# motherboard_v4.net
KiCad netlist of a schematic drawn in EAGLE
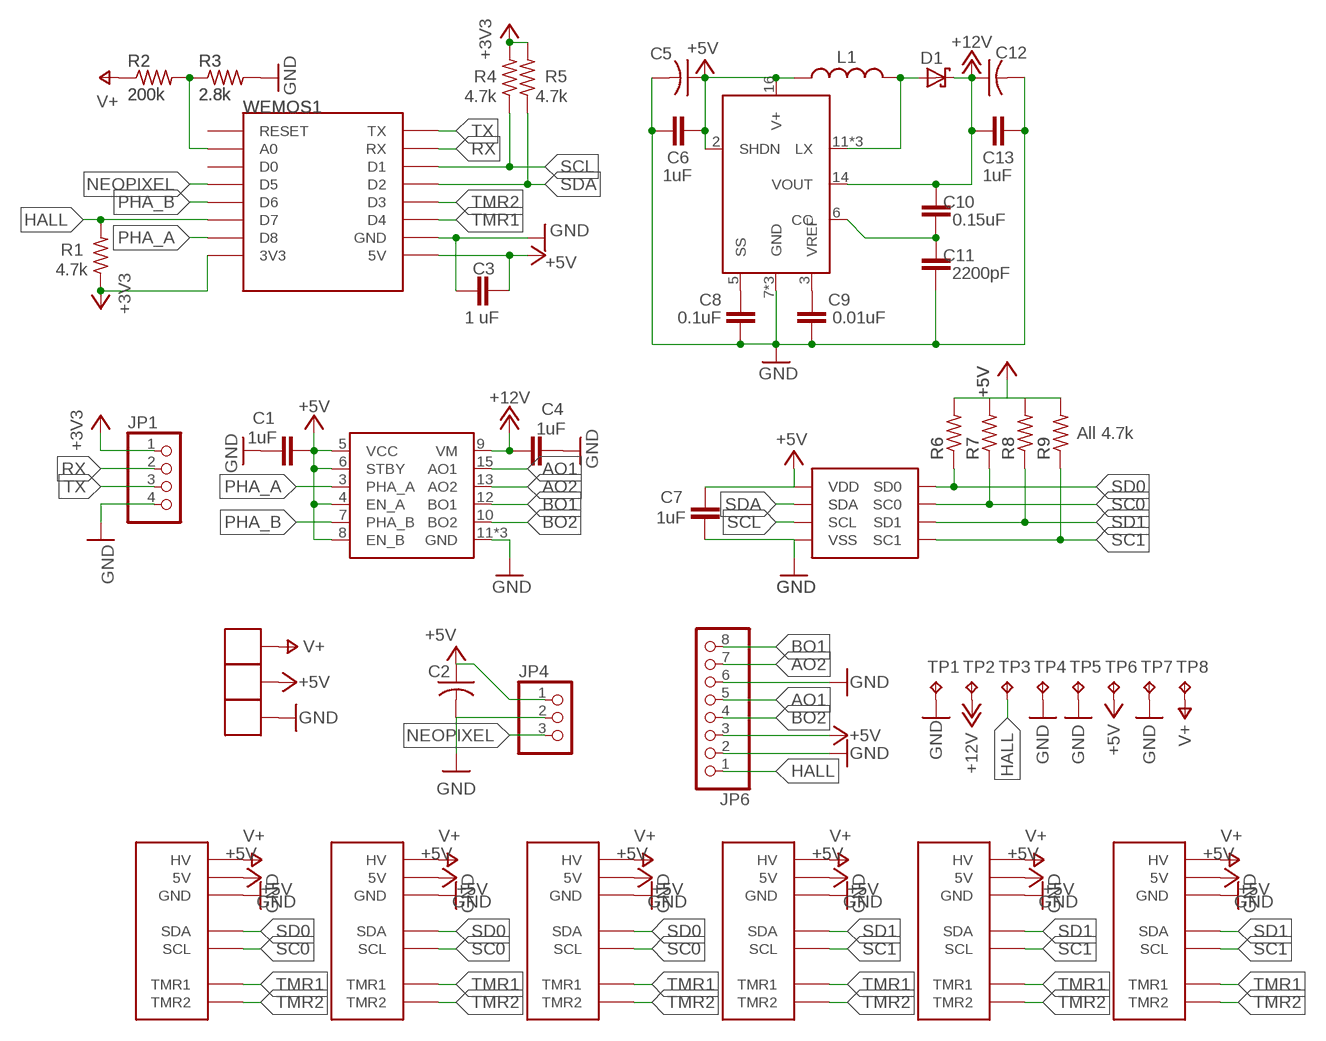
[diagram p0: schematic, sheet 1]

(export (version "E")
  (design (tool "Eeschema 10.0.6"))
  (components
    (comp (ref "C1")
      (value "1uF")
      (footprint "eagle-import:C1206")
      (libsource (lib "eagle-import") (part "C-EUC1206"))
    )
    (comp (ref "C2")
      (value "UCM1H331MNL1GS")
      (footprint "eagle-import:CAPAE1030X1050")
      (libsource (lib "eagle-import") (part "UCM1H331MNL1GS"))
    )
    (comp (ref "C3")
      (value "1 uF")
      (footprint "eagle-import:C1206")
      (libsource (lib "eagle-import") (part "C-EUC1206"))
    )
    (comp (ref "C4")
      (value "1uF")
      (footprint "eagle-import:C1206")
      (libsource (lib "eagle-import") (part "C-EUC1206"))
    )
    (comp (ref "C5")
      (value "UCM1H331MNL1GS")
      (footprint "eagle-import:CAPAE1030X1050")
      (libsource (lib "eagle-import") (part "UCM1H331MNL1GS"))
    )
    (comp (ref "C6")
      (value "1uF")
      (footprint "eagle-import:C1206")
      (libsource (lib "eagle-import") (part "C-EUC1206"))
    )
    (comp (ref "C7")
      (value "1uF")
      (footprint "eagle-import:C1206")
      (libsource (lib "eagle-import") (part "C-EUC1206"))
    )
    (comp (ref "C8")
      (value "0.1uF")
      (footprint "eagle-import:C1206")
      (libsource (lib "eagle-import") (part "C-EUC1206"))
    )
    (comp (ref "C9")
      (value "0.01uF")
      (footprint "eagle-import:C1206")
      (libsource (lib "eagle-import") (part "C-EUC1206"))
    )
    (comp (ref "C10")
      (value "0.15uF")
      (footprint "eagle-import:C1206")
      (libsource (lib "eagle-import") (part "C-EUC1206"))
    )
    (comp (ref "C11")
      (value "2200pF")
      (footprint "eagle-import:C1206")
      (libsource (lib "eagle-import") (part "C-EUC1206"))
    )
    (comp (ref "C12")
      (value "UCM1H331MNL1GS")
      (footprint "eagle-import:CAPAE1030X1050")
      (libsource (lib "eagle-import") (part "UCM1H331MNL1GS"))
    )
    (comp (ref "C13")
      (value "1uF")
      (footprint "eagle-import:C1206")
      (libsource (lib "eagle-import") (part "C-EUC1206"))
    )
    (comp (ref "D1")
      (value "NSR0530H")
      (footprint "eagle-import:SOD2512X100")
      (libsource (lib "eagle-import") (part "NSR0530H"))
    )
    (comp (ref "J1")
      (value "PHOENIX_1731468")
      (footprint "eagle-import:PHOENIX_1731468")
      (libsource (lib "eagle-import") (part "PHOENIX_1731468"))
    )
    (comp (ref "J2")
      (value "PHOENIX_1731468")
      (footprint "eagle-import:PHOENIX_1731468")
      (libsource (lib "eagle-import") (part "PHOENIX_1731468"))
    )
    (comp (ref "J3")
      (value "PHOENIX_1731468")
      (footprint "eagle-import:PHOENIX_1731468")
      (libsource (lib "eagle-import") (part "PHOENIX_1731468"))
    )
    (comp (ref "JP1")
      (value "PINHD-1X4")
      (footprint "eagle-import:1X04")
      (libsource (lib "eagle-import") (part "PINHD-1X4"))
    )
    (comp (ref "JP2")
      (value "PCIE_SOCKET")
      (footprint "eagle-import:PCIE_SOCKET")
      (libsource (lib "eagle-import") (part "PCIE_SOCKET"))
    )
    (comp (ref "JP3")
      (value "PCIE_SOCKET")
      (footprint "eagle-import:PCIE_SOCKET")
      (libsource (lib "eagle-import") (part "PCIE_SOCKET"))
    )
    (comp (ref "JP4")
      (value "PINHD-1X3")
      (footprint "eagle-import:1X03")
      (libsource (lib "eagle-import") (part "PINHD-1X3"))
    )
    (comp (ref "JP5")
      (value "PCIE_SOCKET")
      (footprint "eagle-import:PCIE_SOCKET")
      (libsource (lib "eagle-import") (part "PCIE_SOCKET"))
    )
    (comp (ref "JP6")
      (value "PINHD-1X8")
      (footprint "eagle-import:1X08")
      (libsource (lib "eagle-import") (part "PINHD-1X8"))
    )
    (comp (ref "JP7")
      (value "PCIE_SOCKET")
      (footprint "eagle-import:PCIE_SOCKET")
      (libsource (lib "eagle-import") (part "PCIE_SOCKET"))
    )
    (comp (ref "JP8")
      (value "PCIE_SOCKET")
      (footprint "eagle-import:PCIE_SOCKET")
      (libsource (lib "eagle-import") (part "PCIE_SOCKET"))
    )
    (comp (ref "JP9")
      (value "PCIE_SOCKET")
      (footprint "eagle-import:PCIE_SOCKET")
      (libsource (lib "eagle-import") (part "PCIE_SOCKET"))
    )
    (comp (ref "L1")
      (value "NR6028")
      (footprint "eagle-import:NR6028")
      (libsource (lib "eagle-import") (part "NR6028"))
    )
    (comp (ref "R1")
      (value "4.7k")
      (footprint "eagle-import:R1206")
      (libsource (lib "eagle-import") (part "R-US_R1206"))
    )
    (comp (ref "R2")
      (value "200k")
      (footprint "eagle-import:R1206")
      (libsource (lib "eagle-import") (part "R-US_R1206"))
    )
    (comp (ref "R3")
      (value "2.8k")
      (footprint "eagle-import:R1206")
      (libsource (lib "eagle-import") (part "R-US_R1206"))
    )
    (comp (ref "R4")
      (value "4.7k")
      (footprint "eagle-import:R1206")
      (libsource (lib "eagle-import") (part "R-US_R1206"))
    )
    (comp (ref "R5")
      (value "4.7k")
      (footprint "eagle-import:R1206")
      (libsource (lib "eagle-import") (part "R-US_R1206"))
    )
    (comp (ref "R6")
      (value "R-US_R1206")
      (footprint "eagle-import:R1206")
      (libsource (lib "eagle-import") (part "R-US_R1206"))
    )
    (comp (ref "R7")
      (value "R-US_R1206")
      (footprint "eagle-import:R1206")
      (libsource (lib "eagle-import") (part "R-US_R1206"))
    )
    (comp (ref "R8")
      (value "R-US_R1206")
      (footprint "eagle-import:R1206")
      (libsource (lib "eagle-import") (part "R-US_R1206"))
    )
    (comp (ref "R9")
      (value "R-US_R1206")
      (footprint "eagle-import:R1206")
      (libsource (lib "eagle-import") (part "R-US_R1206"))
    )
    (comp (ref "TP1")
      (value "TPB2,54")
      (footprint "eagle-import:B2,54")
      (libsource (lib "eagle-import") (part "TPB2,54"))
    )
    (comp (ref "TP2")
      (value "TPB2,54")
      (footprint "eagle-import:B2,54")
      (libsource (lib "eagle-import") (part "TPB2,54"))
    )
    (comp (ref "TP3")
      (value "TPB2,54")
      (footprint "eagle-import:B2,54")
      (libsource (lib "eagle-import") (part "TPB2,54"))
    )
    (comp (ref "TP4")
      (value "TPB2,54")
      (footprint "eagle-import:B2,54")
      (libsource (lib "eagle-import") (part "TPB2,54"))
    )
    (comp (ref "TP5")
      (value "TPB2,54")
      (footprint "eagle-import:B2,54")
      (libsource (lib "eagle-import") (part "TPB2,54"))
    )
    (comp (ref "TP6")
      (value "TPB2,54")
      (footprint "eagle-import:B2,54")
      (libsource (lib "eagle-import") (part "TPB2,54"))
    )
    (comp (ref "TP7")
      (value "TPB2,54")
      (footprint "eagle-import:B2,54")
      (libsource (lib "eagle-import") (part "TPB2,54"))
    )
    (comp (ref "TP8")
      (value "TPB2,54")
      (footprint "eagle-import:B2,54")
      (libsource (lib "eagle-import") (part "TPB2,54"))
    )
    (comp (ref "U1")
      (value "TC78H620FNG")
      (footprint "eagle-import:SSOP16")
      (libsource (lib "eagle-import") (part "TC78H620FNG"))
    )
    (comp (ref "U2")
      (value "MAX732")
      (footprint "eagle-import:SOIC127P1032X265-16")
      (libsource (lib "eagle-import") (part "MAX732"))
    )
    (comp (ref "U3")
      (value "PCA9540BDPSOIC8")
      (footprint "eagle-import:SOIC127P599X175-8")
      (libsource (lib "eagle-import") (part "PCA9540BDPSOIC8"))
    )
    (comp (ref "WEMOS1")
      (value "WEMOS-D1-MINISMD")
      (footprint "eagle-import:WEMOS-D1-MINI-SMD")
      (libsource (lib "eagle-import") (part "WEMOS-D1-MINISMD"))
    )
  )
  (nets
    (net (code "1") (name "+3V3") (class "Default")
      (node (ref "JP1") (pin "1") (pinfunction "1_1") (pintype "passive"))
      (node (ref "R1") (pin "1") (pinfunction "1_1") (pintype "passive"))
      (node (ref "R4") (pin "2") (pinfunction "2_2") (pintype "passive"))
      (node (ref "R5") (pin "2") (pinfunction "2_2") (pintype "passive"))
      (node (ref "WEMOS1") (pin "3V3") (pinfunction "3V3_3V3") (pintype "bidirectional"))
    )
    (net (code "2") (name "+5V") (class "Default")
      (node (ref "C1") (pin "2") (pinfunction "2_2") (pintype "passive"))
      (node (ref "C2") (pin "1") (pinfunction "1_1") (pintype "passive"))
      (node (ref "C3") (pin "2") (pinfunction "2_2") (pintype "passive"))
      (node (ref "C5") (pin "1") (pinfunction "1_1") (pintype "passive"))
      (node (ref "C6") (pin "1") (pinfunction "1_1") (pintype "passive"))
      (node (ref "C7") (pin "2") (pinfunction "2_2") (pintype "passive"))
      (node (ref "J2") (pin "P$1") (pinfunction "P$1_P$1") (pintype "bidirectional"))
      (node (ref "J2") (pin "P$2") (pinfunction "P$1_P$2") (pintype "bidirectional"))
      (node (ref "JP2") (pin "5V1") (pinfunction "5V_5V1") (pintype "passive"))
      (node (ref "JP2") (pin "5V2") (pinfunction "5V_5V2") (pintype "passive"))
      (node (ref "JP3") (pin "5V1") (pinfunction "5V_5V1") (pintype "passive"))
      (node (ref "JP3") (pin "5V2") (pinfunction "5V_5V2") (pintype "passive"))
      (node (ref "JP4") (pin "1") (pinfunction "1_1") (pintype "passive"))
      (node (ref "JP5") (pin "5V1") (pinfunction "5V_5V1") (pintype "passive"))
      (node (ref "JP5") (pin "5V2") (pinfunction "5V_5V2") (pintype "passive"))
      (node (ref "JP6") (pin "3") (pinfunction "3_3") (pintype "passive"))
      (node (ref "JP7") (pin "5V1") (pinfunction "5V_5V1") (pintype "passive"))
      (node (ref "JP7") (pin "5V2") (pinfunction "5V_5V2") (pintype "passive"))
      (node (ref "JP8") (pin "5V1") (pinfunction "5V_5V1") (pintype "passive"))
      (node (ref "JP8") (pin "5V2") (pinfunction "5V_5V2") (pintype "passive"))
      (node (ref "JP9") (pin "5V1") (pinfunction "5V_5V1") (pintype "passive"))
      (node (ref "JP9") (pin "5V2") (pinfunction "5V_5V2") (pintype "passive"))
      (node (ref "L1") (pin "1") (pinfunction "1_1") (pintype "passive"))
      (node (ref "R6") (pin "2") (pinfunction "2_2") (pintype "passive"))
      (node (ref "R7") (pin "2") (pinfunction "2_2") (pintype "passive"))
      (node (ref "R8") (pin "2") (pinfunction "2_2") (pintype "passive"))
      (node (ref "R9") (pin "2") (pinfunction "2_2") (pintype "passive"))
      (node (ref "TP6") (pin "TP") (pinfunction "TP_TP") (pintype "input"))
      (node (ref "U1") (pin "4") (pinfunction "EN_A_4") (pintype "bidirectional"))
      (node (ref "U1") (pin "5") (pinfunction "VCC_5") (pintype "bidirectional"))
      (node (ref "U1") (pin "6") (pinfunction "STBY_6") (pintype "bidirectional"))
      (node (ref "U1") (pin "8") (pinfunction "EN_B_8") (pintype "bidirectional"))
      (node (ref "U2") (pin "16") (pinfunction "V+_16") (pintype "passive"))
      (node (ref "U2") (pin "2") (pinfunction "SHDN_2") (pintype "passive"))
      (node (ref "U3") (pin "3") (pinfunction "VDD_3") (pintype "bidirectional"))
      (node (ref "WEMOS1") (pin "5V") (pinfunction "5V_5V") (pintype "bidirectional"))
    )
    (net (code "3") (name "+12V") (class "Default")
      (node (ref "C10") (pin "2") (pinfunction "2_2") (pintype "passive"))
      (node (ref "C12") (pin "1") (pinfunction "1_1") (pintype "passive"))
      (node (ref "C13") (pin "2") (pinfunction "2_2") (pintype "passive"))
      (node (ref "C4") (pin "1") (pinfunction "1_1") (pintype "passive"))
      (node (ref "D1") (pin "1") (pinfunction "C_1") (pintype "passive"))
      (node (ref "TP2") (pin "TP") (pinfunction "TP_TP") (pintype "input"))
      (node (ref "U1") (pin "9") (pinfunction "VM_9") (pintype "bidirectional"))
      (node (ref "U2") (pin "14") (pinfunction "VOUT_14") (pintype "passive"))
    )
    (net (code "4") (name "AO1") (class "Default")
      (node (ref "JP6") (pin "5") (pinfunction "5_5") (pintype "passive"))
      (node (ref "U1") (pin "15") (pinfunction "AO1_15") (pintype "bidirectional"))
    )
    (net (code "5") (name "AO2") (class "Default")
      (node (ref "JP6") (pin "7") (pinfunction "7_7") (pintype "passive"))
      (node (ref "U1") (pin "13") (pinfunction "AO2_13") (pintype "bidirectional"))
    )
    (net (code "6") (name "BO1") (class "Default")
      (node (ref "JP6") (pin "8") (pinfunction "8_8") (pintype "passive"))
      (node (ref "U1") (pin "12") (pinfunction "BO1_12") (pintype "bidirectional"))
    )
    (net (code "7") (name "BO2") (class "Default")
      (node (ref "JP6") (pin "4") (pinfunction "4_4") (pintype "passive"))
      (node (ref "U1") (pin "10") (pinfunction "BO2_10") (pintype "bidirectional"))
    )
    (net (code "8") (name "GND") (class "Default")
      (node (ref "C1") (pin "1") (pinfunction "1_1") (pintype "passive"))
      (node (ref "C11") (pin "1") (pinfunction "1_1") (pintype "passive"))
      (node (ref "C12") (pin "2") (pinfunction "2_2") (pintype "passive"))
      (node (ref "C13") (pin "1") (pinfunction "1_1") (pintype "passive"))
      (node (ref "C2") (pin "2") (pinfunction "2_2") (pintype "passive"))
      (node (ref "C3") (pin "1") (pinfunction "1_1") (pintype "passive"))
      (node (ref "C4") (pin "2") (pinfunction "2_2") (pintype "passive"))
      (node (ref "C5") (pin "2") (pinfunction "2_2") (pintype "passive"))
      (node (ref "C6") (pin "2") (pinfunction "2_2") (pintype "passive"))
      (node (ref "C7") (pin "1") (pinfunction "1_1") (pintype "passive"))
      (node (ref "C8") (pin "1") (pinfunction "1_1") (pintype "passive"))
      (node (ref "C9") (pin "1") (pinfunction "1_1") (pintype "passive"))
      (node (ref "J3") (pin "P$1") (pinfunction "P$1_P$1") (pintype "bidirectional"))
      (node (ref "J3") (pin "P$2") (pinfunction "P$1_P$2") (pintype "bidirectional"))
      (node (ref "JP1") (pin "4") (pinfunction "4_4") (pintype "passive"))
      (node (ref "JP2") (pin "GND1") (pinfunction "GND_GND1") (pintype "passive"))
      (node (ref "JP2") (pin "GND2") (pinfunction "GND_GND2") (pintype "passive"))
      (node (ref "JP3") (pin "GND1") (pinfunction "GND_GND1") (pintype "passive"))
      (node (ref "JP3") (pin "GND2") (pinfunction "GND_GND2") (pintype "passive"))
      (node (ref "JP4") (pin "2") (pinfunction "2_2") (pintype "passive"))
      (node (ref "JP5") (pin "GND1") (pinfunction "GND_GND1") (pintype "passive"))
      (node (ref "JP5") (pin "GND2") (pinfunction "GND_GND2") (pintype "passive"))
      (node (ref "JP6") (pin "2") (pinfunction "2_2") (pintype "passive"))
      (node (ref "JP6") (pin "6") (pinfunction "6_6") (pintype "passive"))
      (node (ref "JP7") (pin "GND1") (pinfunction "GND_GND1") (pintype "passive"))
      (node (ref "JP7") (pin "GND2") (pinfunction "GND_GND2") (pintype "passive"))
      (node (ref "JP8") (pin "GND1") (pinfunction "GND_GND1") (pintype "passive"))
      (node (ref "JP8") (pin "GND2") (pinfunction "GND_GND2") (pintype "passive"))
      (node (ref "JP9") (pin "GND1") (pinfunction "GND_GND1") (pintype "passive"))
      (node (ref "JP9") (pin "GND2") (pinfunction "GND_GND2") (pintype "passive"))
      (node (ref "R3") (pin "2") (pinfunction "2_2") (pintype "passive"))
      (node (ref "TP1") (pin "TP") (pinfunction "TP_TP") (pintype "input"))
      (node (ref "TP4") (pin "TP") (pinfunction "TP_TP") (pintype "input"))
      (node (ref "TP5") (pin "TP") (pinfunction "TP_TP") (pintype "input"))
      (node (ref "TP7") (pin "TP") (pinfunction "TP_TP") (pintype "input"))
      (node (ref "U1") (pin "11") (pinfunction "GND_11") (pintype "bidirectional"))
      (node (ref "U1") (pin "14") (pinfunction "GND_14") (pintype "bidirectional"))
      (node (ref "U1") (pin "16") (pinfunction "GND_16") (pintype "bidirectional"))
      (node (ref "U2") (pin "7") (pinfunction "GND_7") (pintype "passive"))
      (node (ref "U2") (pin "8") (pinfunction "GND_8") (pintype "passive"))
      (node (ref "U2") (pin "9") (pinfunction "GND_9") (pintype "passive"))
      (node (ref "U3") (pin "6") (pinfunction "VSS_6") (pintype "bidirectional"))
      (node (ref "WEMOS1") (pin "GND") (pinfunction "GND_GND") (pintype "bidirectional"))
    )
    (net (code "9") (name "HALL") (class "Default")
      (node (ref "JP6") (pin "1") (pinfunction "1_1") (pintype "passive"))
      (node (ref "R1") (pin "2") (pinfunction "2_2") (pintype "passive"))
      (node (ref "TP3") (pin "TP") (pinfunction "TP_TP") (pintype "input"))
      (node (ref "WEMOS1") (pin "D7") (pinfunction "D7_D7") (pintype "bidirectional"))
    )
    (net (code "10") (name "NEOPIXEL") (class "Default")
      (node (ref "JP4") (pin "3") (pinfunction "3_3") (pintype "passive"))
      (node (ref "WEMOS1") (pin "D5") (pinfunction "D5_D5") (pintype "bidirectional"))
    )
    (net (code "11") (name "Net-(D1-A)") (class "Default")
      (node (ref "D1") (pin "2") (pinfunction "A_2") (pintype "passive"))
      (node (ref "L1") (pin "2") (pinfunction "2_2") (pintype "passive"))
      (node (ref "U2") (pin "11") (pinfunction "LX_11") (pintype "passive"))
      (node (ref "U2") (pin "12") (pinfunction "LX_12") (pintype "passive"))
      (node (ref "U2") (pin "13") (pinfunction "LX_13") (pintype "passive"))
    )
    (net (code "12") (name "Net-(R2-Pad2)") (class "Default")
      (node (ref "R2") (pin "2") (pinfunction "2_2") (pintype "passive"))
      (node (ref "R3") (pin "1") (pinfunction "1_1") (pintype "passive"))
      (node (ref "WEMOS1") (pin "A0") (pinfunction "A0_A0") (pintype "bidirectional"))
    )
    (net (code "13") (name "Net-(U2-CC)") (class "Default")
      (node (ref "C10") (pin "1") (pinfunction "1_1") (pintype "passive"))
      (node (ref "C11") (pin "2") (pinfunction "2_2") (pintype "passive"))
      (node (ref "U2") (pin "6") (pinfunction "CC_6") (pintype "passive"))
    )
    (net (code "14") (name "Net-(U2-SS)") (class "Default")
      (node (ref "C8") (pin "2") (pinfunction "2_2") (pintype "passive"))
      (node (ref "U2") (pin "5") (pinfunction "SS_5") (pintype "passive"))
    )
    (net (code "15") (name "Net-(U2-VREF)") (class "Default")
      (node (ref "C9") (pin "2") (pinfunction "2_2") (pintype "passive"))
      (node (ref "U2") (pin "3") (pinfunction "VREF_3") (pintype "passive"))
    )
    (net (code "16") (name "PHA_A") (class "Default")
      (node (ref "U1") (pin "3") (pinfunction "PHA_A_3") (pintype "bidirectional"))
      (node (ref "WEMOS1") (pin "D8") (pinfunction "D8_D8") (pintype "bidirectional"))
    )
    (net (code "17") (name "PHA_B") (class "Default")
      (node (ref "U1") (pin "7") (pinfunction "PHA_B_7") (pintype "bidirectional"))
      (node (ref "WEMOS1") (pin "D6") (pinfunction "D6_D6") (pintype "bidirectional"))
    )
    (net (code "18") (name "RX") (class "Default")
      (node (ref "JP1") (pin "2") (pinfunction "2_2") (pintype "passive"))
      (node (ref "WEMOS1") (pin "RX") (pinfunction "RX_RX") (pintype "bidirectional"))
    )
    (net (code "19") (name "SC0") (class "Default")
      (node (ref "JP2") (pin "SCL1") (pinfunction "SCL_SCL1") (pintype "bidirectional"))
      (node (ref "JP2") (pin "SCL2") (pinfunction "SCL_SCL2") (pintype "bidirectional"))
      (node (ref "JP3") (pin "SCL1") (pinfunction "SCL_SCL1") (pintype "bidirectional"))
      (node (ref "JP3") (pin "SCL2") (pinfunction "SCL_SCL2") (pintype "bidirectional"))
      (node (ref "JP5") (pin "SCL1") (pinfunction "SCL_SCL1") (pintype "bidirectional"))
      (node (ref "JP5") (pin "SCL2") (pinfunction "SCL_SCL2") (pintype "bidirectional"))
      (node (ref "R7") (pin "1") (pinfunction "1_1") (pintype "passive"))
      (node (ref "U3") (pin "5") (pinfunction "SC0_5") (pintype "bidirectional"))
    )
    (net (code "20") (name "SC1") (class "Default")
      (node (ref "JP7") (pin "SCL1") (pinfunction "SCL_SCL1") (pintype "bidirectional"))
      (node (ref "JP7") (pin "SCL2") (pinfunction "SCL_SCL2") (pintype "bidirectional"))
      (node (ref "JP8") (pin "SCL1") (pinfunction "SCL_SCL1") (pintype "bidirectional"))
      (node (ref "JP8") (pin "SCL2") (pinfunction "SCL_SCL2") (pintype "bidirectional"))
      (node (ref "JP9") (pin "SCL1") (pinfunction "SCL_SCL1") (pintype "bidirectional"))
      (node (ref "JP9") (pin "SCL2") (pinfunction "SCL_SCL2") (pintype "bidirectional"))
      (node (ref "R9") (pin "1") (pinfunction "1_1") (pintype "passive"))
      (node (ref "U3") (pin "8") (pinfunction "SC1_8") (pintype "bidirectional"))
    )
    (net (code "21") (name "SCL") (class "Default")
      (node (ref "R4") (pin "1") (pinfunction "1_1") (pintype "passive"))
      (node (ref "U3") (pin "1") (pinfunction "SCL_1") (pintype "bidirectional"))
      (node (ref "WEMOS1") (pin "D1") (pinfunction "D1_D1") (pintype "bidirectional"))
    )
    (net (code "22") (name "SD0") (class "Default")
      (node (ref "JP2") (pin "SDA1") (pinfunction "SDA_SDA1") (pintype "bidirectional"))
      (node (ref "JP2") (pin "SDA2") (pinfunction "SDA_SDA2") (pintype "bidirectional"))
      (node (ref "JP3") (pin "SDA1") (pinfunction "SDA_SDA1") (pintype "bidirectional"))
      (node (ref "JP3") (pin "SDA2") (pinfunction "SDA_SDA2") (pintype "bidirectional"))
      (node (ref "JP5") (pin "SDA1") (pinfunction "SDA_SDA1") (pintype "bidirectional"))
      (node (ref "JP5") (pin "SDA2") (pinfunction "SDA_SDA2") (pintype "bidirectional"))
      (node (ref "R6") (pin "1") (pinfunction "1_1") (pintype "passive"))
      (node (ref "U3") (pin "4") (pinfunction "SD0_4") (pintype "bidirectional"))
    )
    (net (code "23") (name "SD1") (class "Default")
      (node (ref "JP7") (pin "SDA1") (pinfunction "SDA_SDA1") (pintype "bidirectional"))
      (node (ref "JP7") (pin "SDA2") (pinfunction "SDA_SDA2") (pintype "bidirectional"))
      (node (ref "JP8") (pin "SDA1") (pinfunction "SDA_SDA1") (pintype "bidirectional"))
      (node (ref "JP8") (pin "SDA2") (pinfunction "SDA_SDA2") (pintype "bidirectional"))
      (node (ref "JP9") (pin "SDA1") (pinfunction "SDA_SDA1") (pintype "bidirectional"))
      (node (ref "JP9") (pin "SDA2") (pinfunction "SDA_SDA2") (pintype "bidirectional"))
      (node (ref "R8") (pin "1") (pinfunction "1_1") (pintype "passive"))
      (node (ref "U3") (pin "7") (pinfunction "SD1_7") (pintype "bidirectional"))
    )
    (net (code "24") (name "SDA") (class "Default")
      (node (ref "R5") (pin "1") (pinfunction "1_1") (pintype "passive"))
      (node (ref "U3") (pin "2") (pinfunction "SDA_2") (pintype "bidirectional"))
      (node (ref "WEMOS1") (pin "D2") (pinfunction "D2_D2") (pintype "bidirectional"))
    )
    (net (code "25") (name "TMR1") (class "Default")
      (node (ref "JP2") (pin "TMR1_1") (pinfunction "TMR1_TMR1_1") (pintype "bidirectional"))
      (node (ref "JP2") (pin "TMR1_2") (pinfunction "TMR1_TMR1_2") (pintype "bidirectional"))
      (node (ref "JP3") (pin "TMR1_1") (pinfunction "TMR1_TMR1_1") (pintype "bidirectional"))
      (node (ref "JP3") (pin "TMR1_2") (pinfunction "TMR1_TMR1_2") (pintype "bidirectional"))
      (node (ref "JP5") (pin "TMR1_1") (pinfunction "TMR1_TMR1_1") (pintype "bidirectional"))
      (node (ref "JP5") (pin "TMR1_2") (pinfunction "TMR1_TMR1_2") (pintype "bidirectional"))
      (node (ref "JP7") (pin "TMR1_1") (pinfunction "TMR1_TMR1_1") (pintype "bidirectional"))
      (node (ref "JP7") (pin "TMR1_2") (pinfunction "TMR1_TMR1_2") (pintype "bidirectional"))
      (node (ref "JP8") (pin "TMR1_1") (pinfunction "TMR1_TMR1_1") (pintype "bidirectional"))
      (node (ref "JP8") (pin "TMR1_2") (pinfunction "TMR1_TMR1_2") (pintype "bidirectional"))
      (node (ref "JP9") (pin "TMR1_1") (pinfunction "TMR1_TMR1_1") (pintype "bidirectional"))
      (node (ref "JP9") (pin "TMR1_2") (pinfunction "TMR1_TMR1_2") (pintype "bidirectional"))
      (node (ref "WEMOS1") (pin "D4") (pinfunction "D4_D4") (pintype "bidirectional"))
    )
    (net (code "26") (name "TMR2") (class "Default")
      (node (ref "JP2") (pin "TMR2_1") (pinfunction "TMR2_TMR2_1") (pintype "bidirectional"))
      (node (ref "JP2") (pin "TMR2_2") (pinfunction "TMR2_TMR2_2") (pintype "bidirectional"))
      (node (ref "JP3") (pin "TMR2_1") (pinfunction "TMR2_TMR2_1") (pintype "bidirectional"))
      (node (ref "JP3") (pin "TMR2_2") (pinfunction "TMR2_TMR2_2") (pintype "bidirectional"))
      (node (ref "JP5") (pin "TMR2_1") (pinfunction "TMR2_TMR2_1") (pintype "bidirectional"))
      (node (ref "JP5") (pin "TMR2_2") (pinfunction "TMR2_TMR2_2") (pintype "bidirectional"))
      (node (ref "JP7") (pin "TMR2_1") (pinfunction "TMR2_TMR2_1") (pintype "bidirectional"))
      (node (ref "JP7") (pin "TMR2_2") (pinfunction "TMR2_TMR2_2") (pintype "bidirectional"))
      (node (ref "JP8") (pin "TMR2_1") (pinfunction "TMR2_TMR2_1") (pintype "bidirectional"))
      (node (ref "JP8") (pin "TMR2_2") (pinfunction "TMR2_TMR2_2") (pintype "bidirectional"))
      (node (ref "JP9") (pin "TMR2_1") (pinfunction "TMR2_TMR2_1") (pintype "bidirectional"))
      (node (ref "JP9") (pin "TMR2_2") (pinfunction "TMR2_TMR2_2") (pintype "bidirectional"))
      (node (ref "WEMOS1") (pin "D3") (pinfunction "D3_D3") (pintype "bidirectional"))
    )
    (net (code "27") (name "TX") (class "Default")
      (node (ref "JP1") (pin "3") (pinfunction "3_3") (pintype "passive"))
      (node (ref "WEMOS1") (pin "TX") (pinfunction "TX_TX") (pintype "bidirectional"))
    )
    (net (code "28") (name "V+") (class "Default")
      (node (ref "J1") (pin "P$1") (pinfunction "P$1_P$1") (pintype "bidirectional"))
      (node (ref "J1") (pin "P$2") (pinfunction "P$1_P$2") (pintype "bidirectional"))
      (node (ref "JP2") (pin "HV1") (pinfunction "HV_HV1") (pintype "passive"))
      (node (ref "JP2") (pin "HV2") (pinfunction "HV_HV2") (pintype "passive"))
      (node (ref "JP3") (pin "HV1") (pinfunction "HV_HV1") (pintype "passive"))
      (node (ref "JP3") (pin "HV2") (pinfunction "HV_HV2") (pintype "passive"))
      (node (ref "JP5") (pin "HV1") (pinfunction "HV_HV1") (pintype "passive"))
      (node (ref "JP5") (pin "HV2") (pinfunction "HV_HV2") (pintype "passive"))
      (node (ref "JP7") (pin "HV1") (pinfunction "HV_HV1") (pintype "passive"))
      (node (ref "JP7") (pin "HV2") (pinfunction "HV_HV2") (pintype "passive"))
      (node (ref "JP8") (pin "HV1") (pinfunction "HV_HV1") (pintype "passive"))
      (node (ref "JP8") (pin "HV2") (pinfunction "HV_HV2") (pintype "passive"))
      (node (ref "JP9") (pin "HV1") (pinfunction "HV_HV1") (pintype "passive"))
      (node (ref "JP9") (pin "HV2") (pinfunction "HV_HV2") (pintype "passive"))
      (node (ref "R2") (pin "1") (pinfunction "1_1") (pintype "passive"))
      (node (ref "TP8") (pin "TP") (pinfunction "TP_TP") (pintype "input"))
    )
    (net (code "29") (name "unconnected-(WEMOS1-PadD0)") (class "Default")
      (node (ref "WEMOS1") (pin "D0") (pinfunction "D0_D0") (pintype "bidirectional"))
    )
    (net (code "30") (name "unconnected-(WEMOS1-RESET-PadRST)") (class "Default")
      (node (ref "WEMOS1") (pin "RST") (pinfunction "RESET_RST") (pintype "bidirectional"))
    )
  )
)
